# SMDiDCR.net
KiCad netlist of a schematic drawn in Altium Designer
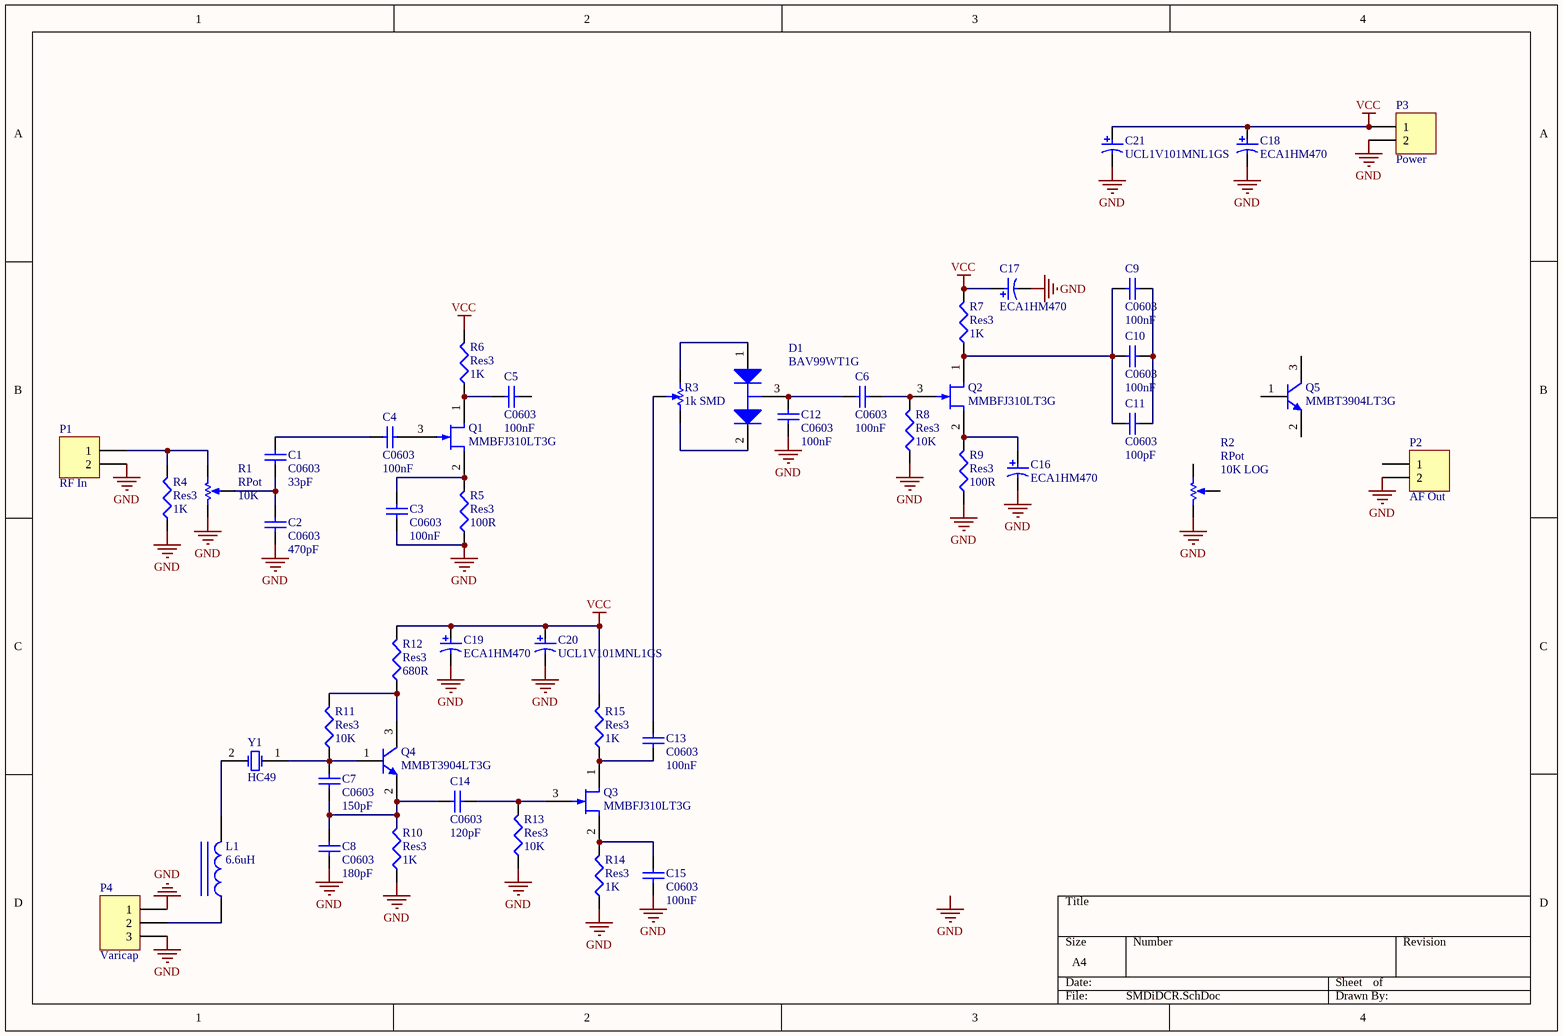
[diagram p0: SMDiDCR.SchDoc]

(export (version "E")
  (design (tool "Eeschema 10.0.6"))
  (components
    (comp (ref "C1")
      (value "C0603")
      (footprint "0603")
      (description "Ceramic Chip Capacitor - Standard")
      (fields (field (name "ALTIUM_VALUE") "33pF") (field (name "PUBLISHER") "Altium Limited"))
      (libsource (lib "KEMET Chip Capacitor") (part "C0603"))
    )
    (comp (ref "C2")
      (value "C0603")
      (footprint "0603")
      (description "Ceramic Chip Capacitor - Standard")
      (fields (field (name "ALTIUM_VALUE") "470pF") (field (name "PUBLISHER") "Altium Limited"))
      (libsource (lib "KEMET Chip Capacitor") (part "C0603"))
    )
    (comp (ref "C3")
      (value "C0603")
      (footprint "0603")
      (description "Ceramic Chip Capacitor - Standard")
      (fields (field (name "ALTIUM_VALUE") "100nF") (field (name "PUBLISHER") "Altium Limited"))
      (libsource (lib "KEMET Chip Capacitor") (part "C0603"))
    )
    (comp (ref "C4")
      (value "C0603")
      (footprint "0603")
      (description "Ceramic Chip Capacitor - Standard")
      (fields (field (name "ALTIUM_VALUE") "100nF") (field (name "PUBLISHER") "Altium Limited"))
      (libsource (lib "KEMET Chip Capacitor") (part "C0603"))
    )
    (comp (ref "C5")
      (value "C0603")
      (footprint "0603")
      (description "Ceramic Chip Capacitor - Standard")
      (fields (field (name "ALTIUM_VALUE") "100nF") (field (name "PUBLISHER") "Altium Limited"))
      (libsource (lib "KEMET Chip Capacitor") (part "C0603"))
    )
    (comp (ref "C6")
      (value "C0603")
      (footprint "0603")
      (description "Ceramic Chip Capacitor - Standard")
      (fields (field (name "ALTIUM_VALUE") "100nF") (field (name "PUBLISHER") "Altium Limited"))
      (libsource (lib "KEMET Chip Capacitor") (part "C0603"))
    )
    (comp (ref "C7")
      (value "C0603")
      (footprint "0603")
      (description "Ceramic Chip Capacitor - Standard")
      (fields (field (name "ALTIUM_VALUE") "150pF") (field (name "PUBLISHER") "Altium Limited"))
      (libsource (lib "KEMET Chip Capacitor") (part "C0603"))
    )
    (comp (ref "C8")
      (value "C0603")
      (footprint "0603")
      (description "Ceramic Chip Capacitor - Standard")
      (fields (field (name "ALTIUM_VALUE") "180pF") (field (name "PUBLISHER") "Altium Limited"))
      (libsource (lib "KEMET Chip Capacitor") (part "C0603"))
    )
    (comp (ref "C9")
      (value "C0603")
      (footprint "0603")
      (description "Ceramic Chip Capacitor - Standard")
      (fields (field (name "ALTIUM_VALUE") "100nF") (field (name "PUBLISHER") "Altium Limited"))
      (libsource (lib "KEMET Chip Capacitor") (part "C0603"))
    )
    (comp (ref "C10")
      (value "C0603")
      (footprint "0603")
      (description "Ceramic Chip Capacitor - Standard")
      (fields (field (name "ALTIUM_VALUE") "100nF") (field (name "PUBLISHER") "Altium Limited"))
      (libsource (lib "KEMET Chip Capacitor") (part "C0603"))
    )
    (comp (ref "C11")
      (value "C0603")
      (footprint "0603")
      (description "Ceramic Chip Capacitor - Standard")
      (fields (field (name "ALTIUM_VALUE") "100pF") (field (name "PUBLISHER") "Altium Limited"))
      (libsource (lib "KEMET Chip Capacitor") (part "C0603"))
    )
    (comp (ref "C12")
      (value "C0603")
      (footprint "0603")
      (description "Ceramic Chip Capacitor - Standard")
      (fields (field (name "ALTIUM_VALUE") "100nF") (field (name "PUBLISHER") "Altium Limited"))
      (libsource (lib "KEMET Chip Capacitor") (part "C0603"))
    )
    (comp (ref "C13")
      (value "C0603")
      (footprint "0603")
      (description "Ceramic Chip Capacitor - Standard")
      (fields (field (name "ALTIUM_VALUE") "100nF") (field (name "PUBLISHER") "Altium Limited"))
      (libsource (lib "KEMET Chip Capacitor") (part "C0603"))
    )
    (comp (ref "C14")
      (value "C0603")
      (footprint "0603")
      (description "Ceramic Chip Capacitor - Standard")
      (fields (field (name "ALTIUM_VALUE") "120pF") (field (name "PUBLISHER") "Altium Limited"))
      (libsource (lib "KEMET Chip Capacitor") (part "C0603"))
    )
    (comp (ref "C15")
      (value "C0603")
      (footprint "0603")
      (description "Ceramic Chip Capacitor - Standard")
      (fields (field (name "ALTIUM_VALUE") "100nF") (field (name "PUBLISHER") "Altium Limited"))
      (libsource (lib "KEMET Chip Capacitor") (part "C0603"))
    )
    (comp (ref "C16")
      (value "ECA1HM470")
      (footprint "CAPPR55-250-1120X630X1220")
      (description "Aluminum Electrolytic Capacitor, 47 uF, +/- 20%, 50 V, -40 to 85 degC, 2-Pin THD, RoHS, Bulk")
      (fields (field (name "MANUFACTURER") "Panasonic") (field (name "TOLERANCE") "20%"))
      (libsource (lib "Altium Content Vault") (part "CAP-P-2"))
    )
    (comp (ref "C17")
      (value "ECA1HM470")
      (footprint "CAPPR55-250-1120X630X1220")
      (description "Aluminum Electrolytic Capacitor, 47 uF, +/- 20%, 50 V, -40 to 85 degC, 2-Pin THD, RoHS, Bulk")
      (fields (field (name "MANUFACTURER") "Panasonic") (field (name "TOLERANCE") "20%"))
      (libsource (lib "Altium Content Vault") (part "CAP-P-2"))
    )
    (comp (ref "C18")
      (value "ECA1HM470")
      (footprint "CAPPR55-250-1120X630X1220")
      (description "Aluminum Electrolytic Capacitor, 47 uF, +/- 20%, 50 V, -40 to 85 degC, 2-Pin THD, RoHS, Bulk")
      (fields (field (name "MANUFACTURER") "Panasonic") (field (name "TOLERANCE") "20%"))
      (libsource (lib "Altium Content Vault") (part "CAP-P-2"))
    )
    (comp (ref "C19")
      (value "ECA1HM470")
      (footprint "CAPPR55-250-1120X630X1220")
      (description "Aluminum Electrolytic Capacitor, 47 uF, +/- 20%, 50 V, -40 to 85 degC, 2-Pin THD, RoHS, Bulk")
      (fields (field (name "MANUFACTURER") "Panasonic") (field (name "TOLERANCE") "20%"))
      (libsource (lib "Altium Content Vault") (part "CAP-P-2"))
    )
    (comp (ref "C20")
      (value "UCL1V101MNL1GS")
      (footprint "NIC-UCL1V101MNL1GS_L")
      (fields (field (name "MANUFACTURER") "Nichicon") (field (name "TOLERANCE") "20%"))
      (libsource (lib "Altium Content Vault") (part "CAP-P-2"))
    )
    (comp (ref "C21")
      (value "UCL1V101MNL1GS")
      (footprint "NIC-UCL1V101MNL1GS_L")
      (fields (field (name "MANUFACTURER") "Nichicon") (field (name "TOLERANCE") "20%"))
      (libsource (lib "Altium Content Vault") (part "CAP-P-2"))
    )
    (comp (ref "D1")
      (value "BAV99WT1G")
      (footprint "ONSC-SOT-323-3-419-04_V")
      (description "Dual Series Switching Diodes, 3-Pin SOT-323, Pb-Free, Tape and Reel")
      (fields (field (name "MANUFACTURER") "On Semiconductor"))
      (libsource (lib "Altium Content Vault") (part "ONSC-D-A1K2C3-3"))
    )
    (comp (ref "L1")
      (value "6.6uH")
      (footprint "AXIAL-0.9")
      (description "Magnetic-Core Inductor")
      (fields (field (name "Comment") "Inductor Iron") (field (name "PUBLISHER") "Altium Limited"))
      (libsource (lib "Miscellaneous Devices") (part "Inductor Iron"))
    )
    (comp (ref "P1")
      (value "RF In")
      (footprint "HDR1X2")
      (description "Header, 2-Pin")
      (fields (field (name "PUBLISHER") "Altium Limited"))
      (libsource (lib "Miscellaneous Connectors") (part "Header 2"))
    )
    (comp (ref "P2")
      (value "AF Out")
      (footprint "HDR1X2")
      (description "Header, 2-Pin")
      (fields (field (name "PUBLISHER") "Altium Limited"))
      (libsource (lib "") (part "Header 2_1"))
    )
    (comp (ref "P3")
      (value "Power")
      (footprint "HDR1X2")
      (description "Header, 2-Pin")
      (fields (field (name "PUBLISHER") "Altium Limited"))
      (libsource (lib "") (part "Header 2_1"))
    )
    (comp (ref "P4")
      (value "Varicap")
      (footprint "HDR1X3")
      (description "Header, 3-Pin")
      (fields (field (name "PUBLISHER") "Altium Limited"))
      (libsource (lib "Miscellaneous Connectors") (part "Header 3"))
    )
    (comp (ref "Q1")
      (value "MMBFJ310LT3G")
      (footprint "ONSC-SOT-23-3-318-08_V")
      (description "JFET - VHF / UHF Amplifier Transistor, N-Channel, 3-Pin SOT-23, Pb-Free, Tape and Reel")
      (fields (field (name "MANUFACTURER") "On Semiconductor"))
      (libsource (lib "Altium Content Vault") (part "ONSC-JFET-D1S2G3-3-B"))
    )
    (comp (ref "Q2")
      (value "MMBFJ310LT3G")
      (footprint "ONSC-SOT-23-3-318-08_V")
      (description "JFET - VHF / UHF Amplifier Transistor, N-Channel, 3-Pin SOT-23, Pb-Free, Tape and Reel")
      (fields (field (name "MANUFACTURER") "On Semiconductor"))
      (libsource (lib "Altium Content Vault") (part "ONSC-JFET-D1S2G3-3-B"))
    )
    (comp (ref "Q3")
      (value "MMBFJ310LT3G")
      (footprint "ONSC-SOT-23-3-318-08_V")
      (description "JFET - VHF / UHF Amplifier Transistor, N-Channel, 3-Pin SOT-23, Pb-Free, Tape and Reel")
      (fields (field (name "MANUFACTURER") "On Semiconductor"))
      (libsource (lib "Altium Content Vault") (part "ONSC-JFET-D1S2G3-3-B"))
    )
    (comp (ref "Q4")
      (value "MMBT3904LT3G")
      (footprint "ONSC-SOT-23-3-318-08_V")
      (description "General Purpose Transistor, NPN Silicon, 3-Pin SOT-23, Pb-Free, Tape and Reel")
      (fields (field (name "MANUFACTURER") "On Semiconductor"))
      (libsource (lib "Altium Content Vault") (part "ONSC-NPN-B1E2C3-3"))
    )
    (comp (ref "Q5")
      (value "MMBT3904LT3G")
      (footprint "ONSC-SOT-23-3-318-08_V")
      (description "General Purpose Transistor, NPN Silicon, 3-Pin SOT-23, Pb-Free, Tape and Reel")
      (fields (field (name "MANUFACTURER") "On Semiconductor"))
      (libsource (lib "Altium Content Vault") (part "ONSC-NPN-B1E2C3-3"))
    )
    (comp (ref "R1")
      (value "RPot")
      (footprint "VR5")
      (description "Potentiometer")
      (fields (field (name "ALTIUM_VALUE") "10K") (field (name "PUBLISHER") "Altium Limited"))
      (libsource (lib "Miscellaneous Devices") (part "RPot"))
    )
    (comp (ref "R2")
      (value "RPot")
      (footprint "VR5")
      (description "Potentiometer")
      (fields (field (name "ALTIUM_VALUE") "10K LOG") (field (name "PUBLISHER") "Altium Limited"))
      (libsource (lib "Miscellaneous Devices") (part "RPot"))
    )
    (comp (ref "R3")
      (value "1k SMD")
      (footprint "POT4MM-2")
      (description "Square Trimming Potentiometer")
      (fields (field (name "PUBLISHER") "Altium Limited"))
      (libsource (lib "Miscellaneous Devices") (part "RPot SM"))
    )
    (comp (ref "R4")
      (value "Res3")
      (footprint "J1-0603")
      (description "Resistor")
      (fields (field (name "ALTIUM_VALUE") "1K") (field (name "PUBLISHER") "Altium Limited"))
      (libsource (lib "Miscellaneous Devices") (part "Res3"))
    )
    (comp (ref "R5")
      (value "Res3")
      (footprint "J1-0603")
      (description "Resistor")
      (fields (field (name "ALTIUM_VALUE") "100R") (field (name "PUBLISHER") "Altium Limited"))
      (libsource (lib "Miscellaneous Devices") (part "Res3"))
    )
    (comp (ref "R6")
      (value "Res3")
      (footprint "J1-0603")
      (description "Resistor")
      (fields (field (name "ALTIUM_VALUE") "1K") (field (name "PUBLISHER") "Altium Limited"))
      (libsource (lib "Miscellaneous Devices") (part "Res3"))
    )
    (comp (ref "R7")
      (value "Res3")
      (footprint "J1-0603")
      (description "Resistor")
      (fields (field (name "ALTIUM_VALUE") "1K") (field (name "PUBLISHER") "Altium Limited"))
      (libsource (lib "Miscellaneous Devices") (part "Res3"))
    )
    (comp (ref "R8")
      (value "Res3")
      (footprint "J1-0603")
      (description "Resistor")
      (fields (field (name "ALTIUM_VALUE") "10K") (field (name "PUBLISHER") "Altium Limited"))
      (libsource (lib "Miscellaneous Devices") (part "Res3"))
    )
    (comp (ref "R9")
      (value "Res3")
      (footprint "J1-0603")
      (description "Resistor")
      (fields (field (name "ALTIUM_VALUE") "100R") (field (name "PUBLISHER") "Altium Limited"))
      (libsource (lib "Miscellaneous Devices") (part "Res3"))
    )
    (comp (ref "R10")
      (value "Res3")
      (footprint "J1-0603")
      (description "Resistor")
      (fields (field (name "ALTIUM_VALUE") "1K") (field (name "PUBLISHER") "Altium Limited"))
      (libsource (lib "Miscellaneous Devices") (part "Res3"))
    )
    (comp (ref "R11")
      (value "Res3")
      (footprint "J1-0603")
      (description "Resistor")
      (fields (field (name "ALTIUM_VALUE") "10K") (field (name "PUBLISHER") "Altium Limited"))
      (libsource (lib "Miscellaneous Devices") (part "Res3"))
    )
    (comp (ref "R12")
      (value "Res3")
      (footprint "J1-0603")
      (description "Resistor")
      (fields (field (name "ALTIUM_VALUE") "680R") (field (name "PUBLISHER") "Altium Limited"))
      (libsource (lib "Miscellaneous Devices") (part "Res3"))
    )
    (comp (ref "R13")
      (value "Res3")
      (footprint "J1-0603")
      (description "Resistor")
      (fields (field (name "ALTIUM_VALUE") "10K") (field (name "PUBLISHER") "Altium Limited"))
      (libsource (lib "Miscellaneous Devices") (part "Res3"))
    )
    (comp (ref "R14")
      (value "Res3")
      (footprint "J1-0603")
      (description "Resistor")
      (fields (field (name "ALTIUM_VALUE") "1K") (field (name "PUBLISHER") "Altium Limited"))
      (libsource (lib "Miscellaneous Devices") (part "Res3"))
    )
    (comp (ref "R15")
      (value "Res3")
      (footprint "J1-0603")
      (description "Resistor")
      (fields (field (name "ALTIUM_VALUE") "1K") (field (name "PUBLISHER") "Altium Limited"))
      (libsource (lib "Miscellaneous Devices") (part "Res3"))
    )
    (comp (ref "Y1")
      (value "HC49")
      (footprint "HC-49U")
      (description "Crystal Oscillator")
      (fields (field (name "PUBLISHER") "Altium Limited"))
      (libsource (lib "ECS Crystal Oscillator") (part "ECS-10-13-1"))
    )
  )
  (nets
    (net (code "1") (name "GND") (class "Default")
      (node (ref "C12") (pin "1") (pinfunction "1_1") (pintype "passive"))
      (node (ref "C15") (pin "2") (pinfunction "2_2") (pintype "passive"))
      (node (ref "C16") (pin "2") (pinfunction "2_2") (pintype "passive"))
      (node (ref "C17") (pin "2") (pinfunction "2_2") (pintype "passive"))
      (node (ref "C18") (pin "2") (pinfunction "2_2") (pintype "passive"))
      (node (ref "C19") (pin "2") (pinfunction "2_2") (pintype "passive"))
      (node (ref "C2") (pin "1") (pinfunction "1_1") (pintype "passive"))
      (node (ref "C20") (pin "2") (pinfunction "2_2") (pintype "passive"))
      (node (ref "C21") (pin "2") (pinfunction "2_2") (pintype "passive"))
      (node (ref "C3") (pin "1") (pinfunction "1_1") (pintype "passive"))
      (node (ref "C8") (pin "1") (pinfunction "1_1") (pintype "passive"))
      (node (ref "P1") (pin "2") (pinfunction "2_2") (pintype "passive"))
      (node (ref "P2") (pin "2") (pinfunction "2_2") (pintype "passive"))
      (node (ref "P3") (pin "2") (pinfunction "2_2") (pintype "passive"))
      (node (ref "P4") (pin "1") (pinfunction "1_1") (pintype "passive"))
      (node (ref "P4") (pin "3") (pinfunction "3_3") (pintype "passive"))
      (node (ref "R1") (pin "2") (pinfunction "BOT_2") (pintype "passive"))
      (node (ref "R10") (pin "1") (pinfunction "1_1") (pintype "passive"))
      (node (ref "R13") (pin "1") (pinfunction "1_1") (pintype "passive"))
      (node (ref "R14") (pin "1") (pinfunction "1_1") (pintype "passive"))
      (node (ref "R2") (pin "2") (pinfunction "BOT_2") (pintype "passive"))
      (node (ref "R4") (pin "1") (pinfunction "1_1") (pintype "passive"))
      (node (ref "R5") (pin "1") (pinfunction "1_1") (pintype "passive"))
      (node (ref "R8") (pin "1") (pinfunction "1_1") (pintype "passive"))
      (node (ref "R9") (pin "1") (pinfunction "1_1") (pintype "passive"))
    )
    (net (code "2") (name "Net-(C1-Pad2)") (class "Default")
      (node (ref "C1") (pin "2") (pinfunction "2_2") (pintype "passive"))
      (node (ref "C4") (pin "2") (pinfunction "2_2") (pintype "passive"))
    )
    (net (code "3") (name "Net-(C10-Pad2)") (class "Default")
      (node (ref "C10") (pin "2") (pinfunction "2_2") (pintype "passive"))
      (node (ref "C11") (pin "2") (pinfunction "2_2") (pintype "passive"))
      (node (ref "C9") (pin "2") (pinfunction "2_2") (pintype "passive"))
    )
    (net (code "4") (name "Net-(C13-Pad2)") (class "Default")
      (node (ref "C13") (pin "2") (pinfunction "2_2") (pintype "passive"))
      (node (ref "R3") (pin "W") (pinfunction "W_W") (pintype "passive"))
    )
    (net (code "5") (name "Net-(D1-A)") (class "Default")
      (node (ref "D1") (pin "1") (pinfunction "A_1") (pintype "passive"))
      (node (ref "R3") (pin "CCW") (pinfunction "-_CCW") (pintype "passive"))
    )
    (net (code "6") (name "Net-(D1-K)") (class "Default")
      (node (ref "D1") (pin "2") (pinfunction "K_2") (pintype "passive"))
      (node (ref "R3") (pin "CW") (pinfunction "+_CW") (pintype "passive"))
    )
    (net (code "7") (name "Net-(D1-K{slash}A)") (class "Default")
      (node (ref "C12") (pin "2") (pinfunction "2_2") (pintype "passive"))
      (node (ref "C6") (pin "1") (pinfunction "1_1") (pintype "passive"))
      (node (ref "D1") (pin "3") (pinfunction "K/A_3") (pintype "passive"))
    )
    (net (code "8") (name "Net-(L1-Pad1)") (class "Default")
      (node (ref "L1") (pin "1") (pinfunction "1_1") (pintype "passive"))
      (node (ref "P4") (pin "2") (pinfunction "2_2") (pintype "passive"))
    )
    (net (code "9") (name "Net-(Q1-D)") (class "Default")
      (node (ref "C5") (pin "2") (pinfunction "2_2") (pintype "passive"))
      (node (ref "Q1") (pin "1") (pinfunction "D_1") (pintype "passive"))
      (node (ref "R6") (pin "1") (pinfunction "1_1") (pintype "passive"))
    )
    (net (code "10") (name "Net-(Q1-G)") (class "Default")
      (node (ref "C4") (pin "1") (pinfunction "1_1") (pintype "passive"))
      (node (ref "Q1") (pin "3") (pinfunction "G_3") (pintype "passive"))
    )
    (net (code "11") (name "Net-(Q1-S)") (class "Default")
      (node (ref "C3") (pin "2") (pinfunction "2_2") (pintype "passive"))
      (node (ref "Q1") (pin "2") (pinfunction "S_2") (pintype "passive"))
      (node (ref "R5") (pin "2") (pinfunction "2_2") (pintype "passive"))
    )
    (net (code "12") (name "Net-(Q2-D)") (class "Default")
      (node (ref "C10") (pin "1") (pinfunction "1_1") (pintype "passive"))
      (node (ref "C11") (pin "1") (pinfunction "1_1") (pintype "passive"))
      (node (ref "C9") (pin "1") (pinfunction "1_1") (pintype "passive"))
      (node (ref "Q2") (pin "1") (pinfunction "D_1") (pintype "passive"))
      (node (ref "R7") (pin "1") (pinfunction "1_1") (pintype "passive"))
    )
    (net (code "13") (name "Net-(Q2-G)") (class "Default")
      (node (ref "C6") (pin "2") (pinfunction "2_2") (pintype "passive"))
      (node (ref "Q2") (pin "3") (pinfunction "G_3") (pintype "passive"))
      (node (ref "R8") (pin "2") (pinfunction "2_2") (pintype "passive"))
    )
    (net (code "14") (name "Net-(Q2-S)") (class "Default")
      (node (ref "C16") (pin "1") (pinfunction "1_1") (pintype "passive"))
      (node (ref "Q2") (pin "2") (pinfunction "S_2") (pintype "passive"))
      (node (ref "R9") (pin "2") (pinfunction "2_2") (pintype "passive"))
    )
    (net (code "15") (name "Net-(Q3-D)") (class "Default")
      (node (ref "C13") (pin "1") (pinfunction "1_1") (pintype "passive"))
      (node (ref "Q3") (pin "1") (pinfunction "D_1") (pintype "passive"))
      (node (ref "R15") (pin "1") (pinfunction "1_1") (pintype "passive"))
    )
    (net (code "16") (name "Net-(Q3-G)") (class "Default")
      (node (ref "C14") (pin "1") (pinfunction "1_1") (pintype "passive"))
      (node (ref "Q3") (pin "3") (pinfunction "G_3") (pintype "passive"))
      (node (ref "R13") (pin "2") (pinfunction "2_2") (pintype "passive"))
    )
    (net (code "17") (name "Net-(Q3-S)") (class "Default")
      (node (ref "C15") (pin "1") (pinfunction "1_1") (pintype "passive"))
      (node (ref "Q3") (pin "2") (pinfunction "S_2") (pintype "passive"))
      (node (ref "R14") (pin "2") (pinfunction "2_2") (pintype "passive"))
    )
    (net (code "18") (name "Net-(Q4-B)") (class "Default")
      (node (ref "C7") (pin "2") (pinfunction "2_2") (pintype "passive"))
      (node (ref "Q4") (pin "1") (pinfunction "B_1") (pintype "passive"))
      (node (ref "R11") (pin "1") (pinfunction "1_1") (pintype "passive"))
      (node (ref "Y1") (pin "1") (pinfunction "OSC1_1") (pintype "passive"))
    )
    (net (code "19") (name "Net-(Q4-C)") (class "Default")
      (node (ref "Q4") (pin "3") (pinfunction "C_3") (pintype "passive"))
      (node (ref "R11") (pin "2") (pinfunction "2_2") (pintype "passive"))
      (node (ref "R12") (pin "1") (pinfunction "1_1") (pintype "passive"))
    )
    (net (code "20") (name "Net-(Q4-E)") (class "Default")
      (node (ref "C14") (pin "2") (pinfunction "2_2") (pintype "passive"))
      (node (ref "C7") (pin "1") (pinfunction "1_1") (pintype "passive"))
      (node (ref "C8") (pin "2") (pinfunction "2_2") (pintype "passive"))
      (node (ref "Q4") (pin "2") (pinfunction "E_2") (pintype "passive"))
      (node (ref "R10") (pin "2") (pinfunction "2_2") (pintype "passive"))
    )
    (net (code "21") (name "Net-(R1-TAP)") (class "Default")
      (node (ref "C1") (pin "1") (pinfunction "1_1") (pintype "passive"))
      (node (ref "C2") (pin "2") (pinfunction "2_2") (pintype "passive"))
      (node (ref "R1") (pin "3") (pinfunction "TAP_3") (pintype "passive"))
    )
    (net (code "22") (name "Net-(R1-TOP)") (class "Default")
      (node (ref "P1") (pin "1") (pinfunction "1_1") (pintype "passive"))
      (node (ref "R1") (pin "1") (pinfunction "TOP_1") (pintype "passive"))
      (node (ref "R4") (pin "2") (pinfunction "2_2") (pintype "passive"))
    )
    (net (code "23") (name "Net-(Y1-OSC2)") (class "Default")
      (node (ref "L1") (pin "2") (pinfunction "2_2") (pintype "passive"))
      (node (ref "Y1") (pin "2") (pinfunction "OSC2_2") (pintype "passive"))
    )
    (net (code "24") (name "VCC") (class "Default")
      (node (ref "C17") (pin "1") (pinfunction "1_1") (pintype "passive"))
      (node (ref "C18") (pin "1") (pinfunction "1_1") (pintype "passive"))
      (node (ref "C19") (pin "1") (pinfunction "1_1") (pintype "passive"))
      (node (ref "C20") (pin "1") (pinfunction "1_1") (pintype "passive"))
      (node (ref "C21") (pin "1") (pinfunction "1_1") (pintype "passive"))
      (node (ref "P3") (pin "1") (pinfunction "1_1") (pintype "passive"))
      (node (ref "R12") (pin "2") (pinfunction "2_2") (pintype "passive"))
      (node (ref "R15") (pin "2") (pinfunction "2_2") (pintype "passive"))
      (node (ref "R6") (pin "2") (pinfunction "2_2") (pintype "passive"))
      (node (ref "R7") (pin "2") (pinfunction "2_2") (pintype "passive"))
    )
    (net (code "25") (name "unconnected-(C5-Pad1)") (class "Default")
      (node (ref "C5") (pin "1") (pinfunction "1_1") (pintype "passive"))
    )
    (net (code "26") (name "unconnected-(P2-Pad1)") (class "Default")
      (node (ref "P2") (pin "1") (pinfunction "1_1") (pintype "passive"))
    )
    (net (code "27") (name "unconnected-(Q5-B-Pad1)") (class "Default")
      (node (ref "Q5") (pin "1") (pinfunction "B_1") (pintype "passive"))
    )
    (net (code "28") (name "unconnected-(Q5-C-Pad3)") (class "Default")
      (node (ref "Q5") (pin "3") (pinfunction "C_3") (pintype "passive"))
    )
    (net (code "29") (name "unconnected-(Q5-E-Pad2)") (class "Default")
      (node (ref "Q5") (pin "2") (pinfunction "E_2") (pintype "passive"))
    )
    (net (code "30") (name "unconnected-(R2-TAP-Pad3)") (class "Default")
      (node (ref "R2") (pin "3") (pinfunction "TAP_3") (pintype "passive"))
    )
    (net (code "31") (name "unconnected-(R2-TOP-Pad1)") (class "Default")
      (node (ref "R2") (pin "1") (pinfunction "TOP_1") (pintype "passive"))
    )
  )
)
